# IOIO-NXT-V1.net
KiCad netlist of a schematic drawn in EAGLE
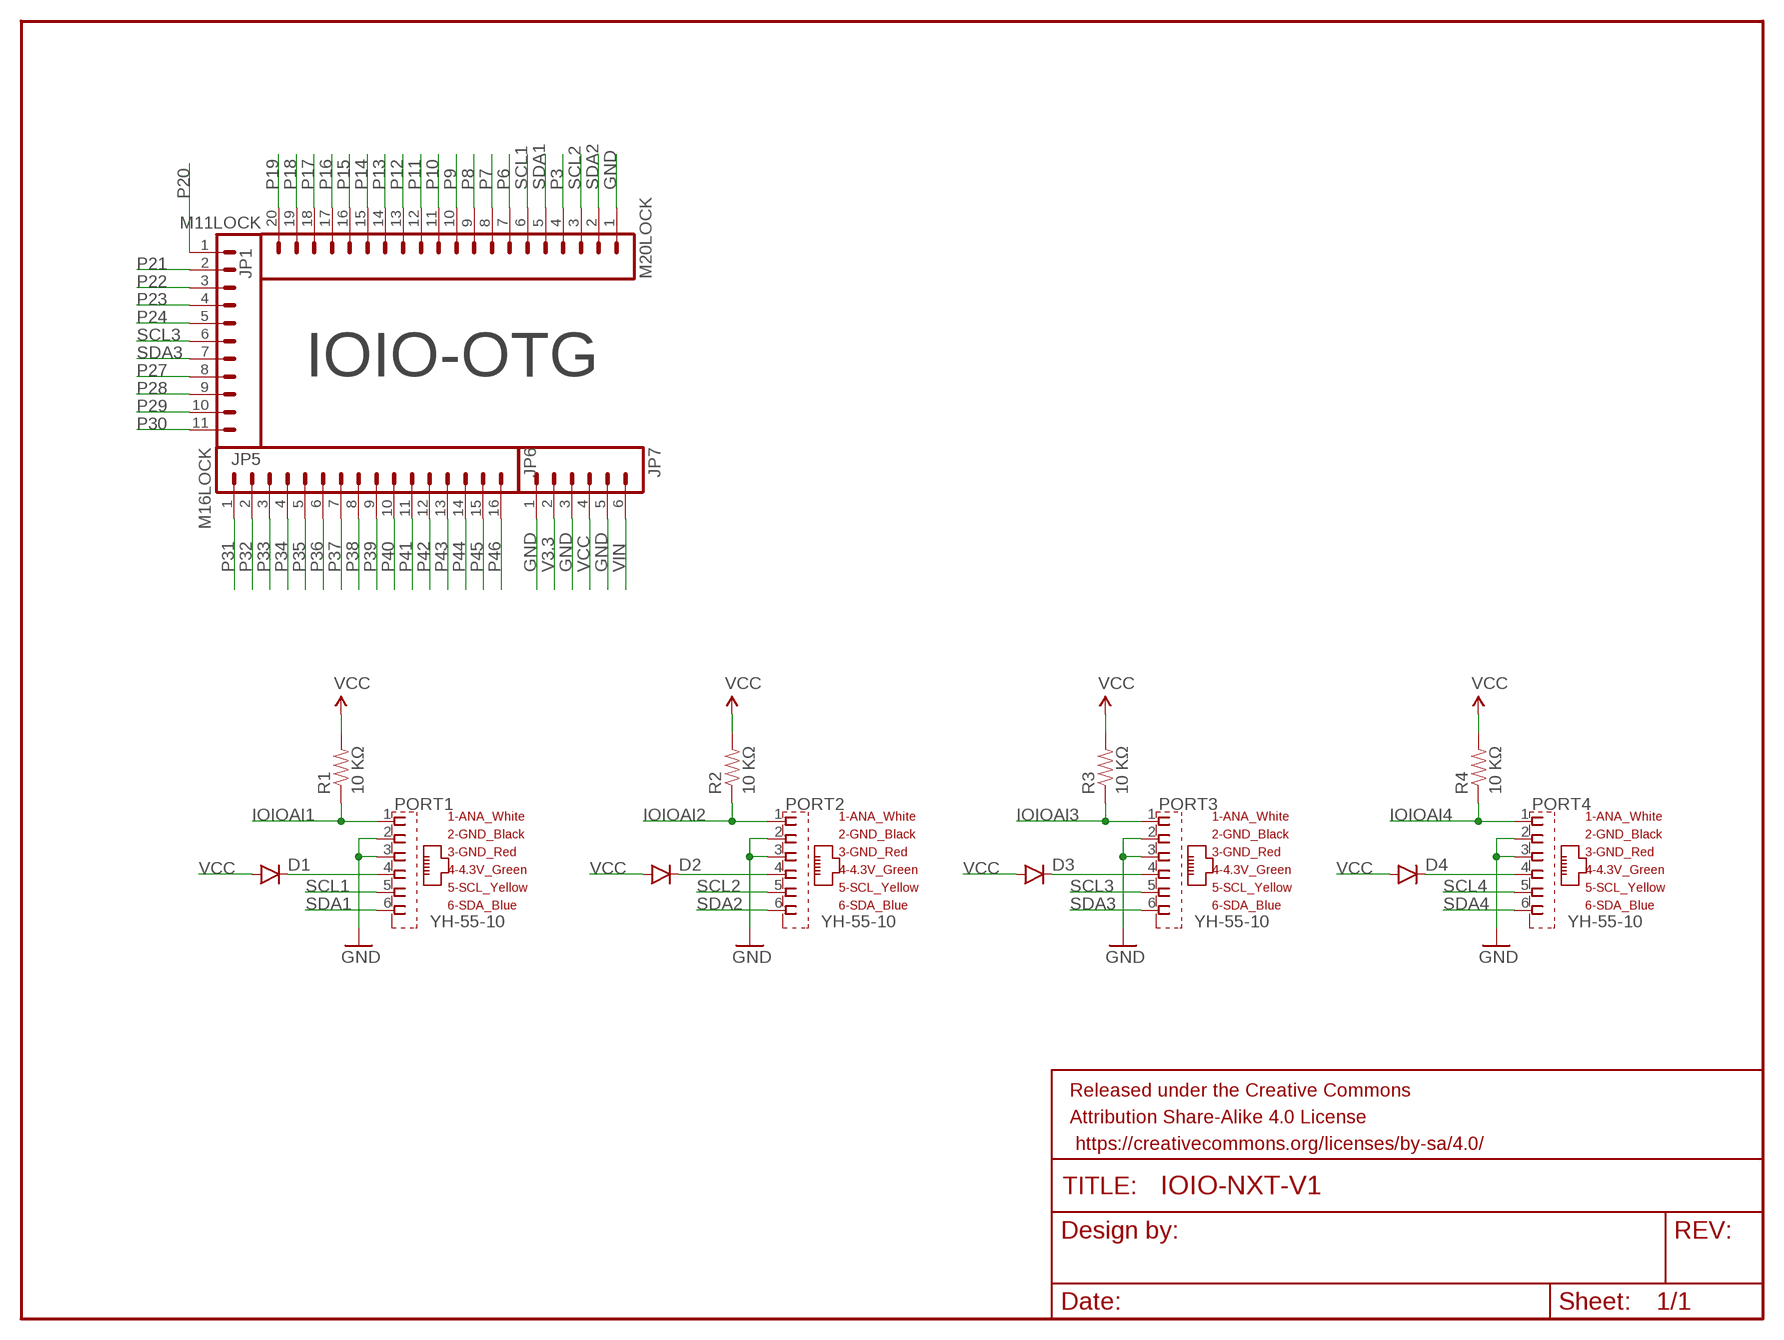
[diagram p0: schematic, sheet 1]

(export (version "E")
  (design (tool "Eeschema 10.0.6"))
  (components
    (comp (ref "D1")
      (value "DIODE")
      (footprint "eagle-import:DIODE-1N4001-KIT")
      (libsource (lib "eagle-import") (part "DIODE"))
    )
    (comp (ref "D2")
      (value "DIODE")
      (footprint "eagle-import:DIODE-1N4001-KIT")
      (libsource (lib "eagle-import") (part "DIODE"))
    )
    (comp (ref "D3")
      (value "DIODE")
      (footprint "eagle-import:DIODE-1N4001-KIT")
      (libsource (lib "eagle-import") (part "DIODE"))
    )
    (comp (ref "D4")
      (value "DIODE")
      (footprint "eagle-import:DIODE-1N4001-KIT")
      (libsource (lib "eagle-import") (part "DIODE"))
    )
    (comp (ref "FRAME1")
      (value "FRAME-LETTER")
      (footprint "eagle-import:CREATIVE_COMMONS")
      (libsource (lib "eagle-import") (part "FRAME-LETTER"))
    )
    (comp (ref "JP1")
      (value "M20LOCK")
      (footprint "eagle-import:1X20_LOCK")
      (libsource (lib "eagle-import") (part "M20LOCK"))
    )
    (comp (ref "JP5")
      (value "M11LOCK")
      (footprint "eagle-import:1X11_LOCK")
      (libsource (lib "eagle-import") (part "M11LOCK"))
    )
    (comp (ref "JP6")
      (value "M16LOCK")
      (footprint "eagle-import:1X16_LOCK")
      (libsource (lib "eagle-import") (part "M16LOCK"))
    )
    (comp (ref "JP7")
      (value "M06LOCK")
      (footprint "eagle-import:1X06_LOCK")
      (libsource (lib "eagle-import") (part "M06LOCK"))
    )
    (comp (ref "PORT1")
      (value "YH-55-10")
      (footprint "eagle-import:YH-55-10")
      (libsource (lib "eagle-import") (part "YH-55-10"))
    )
    (comp (ref "PORT2")
      (value "YH-55-10")
      (footprint "eagle-import:YH-55-10")
      (libsource (lib "eagle-import") (part "YH-55-10"))
    )
    (comp (ref "PORT3")
      (value "YH-55-10")
      (footprint "eagle-import:YH-55-10")
      (libsource (lib "eagle-import") (part "YH-55-10"))
    )
    (comp (ref "PORT4")
      (value "YH-55-10")
      (footprint "eagle-import:YH-55-10")
      (libsource (lib "eagle-import") (part "YH-55-10"))
    )
    (comp (ref "R1")
      (value "10 KΩ")
      (footprint "eagle-import:AXIAL-0.4")
      (libsource (lib "eagle-import") (part "RESISTORPTH-1/4W"))
    )
    (comp (ref "R2")
      (value "10 KΩ")
      (footprint "eagle-import:AXIAL-0.4")
      (libsource (lib "eagle-import") (part "RESISTORPTH-1/4W"))
    )
    (comp (ref "R3")
      (value "10 KΩ")
      (footprint "eagle-import:AXIAL-0.4")
      (libsource (lib "eagle-import") (part "RESISTORPTH-1/4W"))
    )
    (comp (ref "R4")
      (value "10 KΩ")
      (footprint "eagle-import:AXIAL-0.4")
      (libsource (lib "eagle-import") (part "RESISTORPTH-1/4W"))
    )
  )
  (nets
    (net (code "1") (name "/IOIOAI1") (class "Default")
      (node (ref "PORT1") (pin "1") (pinfunction "1_ANA_WHITE_1") (pintype "passive"))
      (node (ref "R1") (pin "P$1") (pinfunction "1_P$1") (pintype "passive"))
    )
    (net (code "2") (name "/IOIOAI2") (class "Default")
      (node (ref "PORT2") (pin "1") (pinfunction "1_ANA_WHITE_1") (pintype "passive"))
      (node (ref "R2") (pin "P$1") (pinfunction "1_P$1") (pintype "passive"))
    )
    (net (code "3") (name "/IOIOAI3") (class "Default")
      (node (ref "PORT3") (pin "1") (pinfunction "1_ANA_WHITE_1") (pintype "passive"))
      (node (ref "R3") (pin "P$1") (pinfunction "1_P$1") (pintype "passive"))
    )
    (net (code "4") (name "/IOIOAI4") (class "Default")
      (node (ref "PORT4") (pin "1") (pinfunction "1_ANA_WHITE_1") (pintype "passive"))
      (node (ref "R4") (pin "P$1") (pinfunction "1_P$1") (pintype "passive"))
    )
    (net (code "5") (name "/P3") (class "Default")
      (node (ref "JP1") (pin "4") (pinfunction "4_4") (pintype "passive"))
    )
    (net (code "6") (name "/P6") (class "Default")
      (node (ref "JP1") (pin "7") (pinfunction "7_7") (pintype "passive"))
    )
    (net (code "7") (name "/P7") (class "Default")
      (node (ref "JP1") (pin "8") (pinfunction "8_8") (pintype "passive"))
    )
    (net (code "8") (name "/P8") (class "Default")
      (node (ref "JP1") (pin "9") (pinfunction "9_9") (pintype "passive"))
    )
    (net (code "9") (name "/P9") (class "Default")
      (node (ref "JP1") (pin "10") (pinfunction "10_10") (pintype "passive"))
    )
    (net (code "10") (name "/P10") (class "Default")
      (node (ref "JP1") (pin "11") (pinfunction "11_11") (pintype "passive"))
    )
    (net (code "11") (name "/P11") (class "Default")
      (node (ref "JP1") (pin "12") (pinfunction "12_12") (pintype "passive"))
    )
    (net (code "12") (name "/P12") (class "Default")
      (node (ref "JP1") (pin "13") (pinfunction "13_13") (pintype "passive"))
    )
    (net (code "13") (name "/P13") (class "Default")
      (node (ref "JP1") (pin "14") (pinfunction "14_14") (pintype "passive"))
    )
    (net (code "14") (name "/P14") (class "Default")
      (node (ref "JP1") (pin "15") (pinfunction "15_15") (pintype "passive"))
    )
    (net (code "15") (name "/P15") (class "Default")
      (node (ref "JP1") (pin "16") (pinfunction "16_16") (pintype "passive"))
    )
    (net (code "16") (name "/P16") (class "Default")
      (node (ref "JP1") (pin "17") (pinfunction "17_17") (pintype "passive"))
    )
    (net (code "17") (name "/P17") (class "Default")
      (node (ref "JP1") (pin "18") (pinfunction "18_18") (pintype "passive"))
    )
    (net (code "18") (name "/P18") (class "Default")
      (node (ref "JP1") (pin "19") (pinfunction "19_19") (pintype "passive"))
    )
    (net (code "19") (name "/P19") (class "Default")
      (node (ref "JP1") (pin "20") (pinfunction "20_20") (pintype "passive"))
    )
    (net (code "20") (name "/P20") (class "Default")
      (node (ref "JP5") (pin "1") (pinfunction "1_1") (pintype "passive"))
    )
    (net (code "21") (name "/P21") (class "Default")
      (node (ref "JP5") (pin "2") (pinfunction "2_2") (pintype "passive"))
    )
    (net (code "22") (name "/P22") (class "Default")
      (node (ref "JP5") (pin "3") (pinfunction "3_3") (pintype "passive"))
    )
    (net (code "23") (name "/P23") (class "Default")
      (node (ref "JP5") (pin "4") (pinfunction "4_4") (pintype "passive"))
    )
    (net (code "24") (name "/P24") (class "Default")
      (node (ref "JP5") (pin "5") (pinfunction "5_5") (pintype "passive"))
    )
    (net (code "25") (name "/P27") (class "Default")
      (node (ref "JP5") (pin "8") (pinfunction "8_8") (pintype "passive"))
    )
    (net (code "26") (name "/P28") (class "Default")
      (node (ref "JP5") (pin "9") (pinfunction "9_9") (pintype "passive"))
    )
    (net (code "27") (name "/P29") (class "Default")
      (node (ref "JP5") (pin "10") (pinfunction "10_10") (pintype "passive"))
    )
    (net (code "28") (name "/P30") (class "Default")
      (node (ref "JP5") (pin "11") (pinfunction "11_11") (pintype "passive"))
    )
    (net (code "29") (name "/P31") (class "Default")
      (node (ref "JP6") (pin "1") (pinfunction "1_1") (pintype "passive"))
    )
    (net (code "30") (name "/P32") (class "Default")
      (node (ref "JP6") (pin "2") (pinfunction "2_2") (pintype "passive"))
    )
    (net (code "31") (name "/P33") (class "Default")
      (node (ref "JP6") (pin "3") (pinfunction "3_3") (pintype "passive"))
    )
    (net (code "32") (name "/P34") (class "Default")
      (node (ref "JP6") (pin "4") (pinfunction "4_4") (pintype "passive"))
    )
    (net (code "33") (name "/P35") (class "Default")
      (node (ref "JP6") (pin "5") (pinfunction "5_5") (pintype "passive"))
    )
    (net (code "34") (name "/P36") (class "Default")
      (node (ref "JP6") (pin "6") (pinfunction "6_6") (pintype "passive"))
    )
    (net (code "35") (name "/P37") (class "Default")
      (node (ref "JP6") (pin "7") (pinfunction "7_7") (pintype "passive"))
    )
    (net (code "36") (name "/P38") (class "Default")
      (node (ref "JP6") (pin "8") (pinfunction "8_8") (pintype "passive"))
    )
    (net (code "37") (name "/P39") (class "Default")
      (node (ref "JP6") (pin "9") (pinfunction "9_9") (pintype "passive"))
    )
    (net (code "38") (name "/P40") (class "Default")
      (node (ref "JP6") (pin "10") (pinfunction "10_10") (pintype "passive"))
    )
    (net (code "39") (name "/P41") (class "Default")
      (node (ref "JP6") (pin "11") (pinfunction "11_11") (pintype "passive"))
    )
    (net (code "40") (name "/P42") (class "Default")
      (node (ref "JP6") (pin "12") (pinfunction "12_12") (pintype "passive"))
    )
    (net (code "41") (name "/P43") (class "Default")
      (node (ref "JP6") (pin "13") (pinfunction "13_13") (pintype "passive"))
    )
    (net (code "42") (name "/P44") (class "Default")
      (node (ref "JP6") (pin "14") (pinfunction "14_14") (pintype "passive"))
    )
    (net (code "43") (name "/P45") (class "Default")
      (node (ref "JP6") (pin "15") (pinfunction "15_15") (pintype "passive"))
    )
    (net (code "44") (name "/P46") (class "Default")
      (node (ref "JP6") (pin "16") (pinfunction "16_16") (pintype "passive"))
    )
    (net (code "45") (name "/SCL1") (class "Default")
      (node (ref "JP1") (pin "6") (pinfunction "6_6") (pintype "passive"))
      (node (ref "PORT1") (pin "5") (pinfunction "5_SCL_YELLOW_5") (pintype "passive"))
    )
    (net (code "46") (name "/SCL2") (class "Default")
      (node (ref "JP1") (pin "3") (pinfunction "3_3") (pintype "passive"))
      (node (ref "PORT2") (pin "5") (pinfunction "5_SCL_YELLOW_5") (pintype "passive"))
    )
    (net (code "47") (name "/SCL3") (class "Default")
      (node (ref "JP5") (pin "6") (pinfunction "6_6") (pintype "passive"))
      (node (ref "PORT3") (pin "5") (pinfunction "5_SCL_YELLOW_5") (pintype "passive"))
    )
    (net (code "48") (name "/SCL4") (class "Default")
      (node (ref "PORT4") (pin "5") (pinfunction "5_SCL_YELLOW_5") (pintype "passive"))
    )
    (net (code "49") (name "/SDA1") (class "Default")
      (node (ref "JP1") (pin "5") (pinfunction "5_5") (pintype "passive"))
      (node (ref "PORT1") (pin "6") (pinfunction "6_SDA_BLUE_6") (pintype "passive"))
    )
    (net (code "50") (name "/SDA2") (class "Default")
      (node (ref "JP1") (pin "2") (pinfunction "2_2") (pintype "passive"))
      (node (ref "PORT2") (pin "6") (pinfunction "6_SDA_BLUE_6") (pintype "passive"))
    )
    (net (code "51") (name "/SDA3") (class "Default")
      (node (ref "JP5") (pin "7") (pinfunction "7_7") (pintype "passive"))
      (node (ref "PORT3") (pin "6") (pinfunction "6_SDA_BLUE_6") (pintype "passive"))
    )
    (net (code "52") (name "/SDA4") (class "Default")
      (node (ref "PORT4") (pin "6") (pinfunction "6_SDA_BLUE_6") (pintype "passive"))
    )
    (net (code "53") (name "/V3.3") (class "Default")
      (node (ref "JP7") (pin "2") (pinfunction "2_2") (pintype "passive"))
    )
    (net (code "54") (name "/VIN") (class "Default")
      (node (ref "JP7") (pin "6") (pinfunction "6_6") (pintype "passive"))
    )
    (net (code "55") (name "GND") (class "Default")
      (node (ref "JP1") (pin "1") (pinfunction "1_1") (pintype "passive"))
      (node (ref "JP7") (pin "1") (pinfunction "1_1") (pintype "passive"))
      (node (ref "JP7") (pin "3") (pinfunction "3_3") (pintype "passive"))
      (node (ref "JP7") (pin "5") (pinfunction "5_5") (pintype "passive"))
      (node (ref "PORT1") (pin "2") (pinfunction "2_GND_BLACK_2") (pintype "passive"))
      (node (ref "PORT1") (pin "3") (pinfunction "3_GND_RED_3") (pintype "passive"))
      (node (ref "PORT2") (pin "2") (pinfunction "2_GND_BLACK_2") (pintype "passive"))
      (node (ref "PORT2") (pin "3") (pinfunction "3_GND_RED_3") (pintype "passive"))
      (node (ref "PORT3") (pin "2") (pinfunction "2_GND_BLACK_2") (pintype "passive"))
      (node (ref "PORT3") (pin "3") (pinfunction "3_GND_RED_3") (pintype "passive"))
      (node (ref "PORT4") (pin "2") (pinfunction "2_GND_BLACK_2") (pintype "passive"))
      (node (ref "PORT4") (pin "3") (pinfunction "3_GND_RED_3") (pintype "passive"))
    )
    (net (code "56") (name "Net-(PORT1-4_4.3V_GREEN)") (class "Default")
      (node (ref "D1") (pin "C") (pinfunction "C_C") (pintype "passive"))
      (node (ref "PORT1") (pin "4") (pinfunction "4_4.3V_GREEN_4") (pintype "passive"))
    )
    (net (code "57") (name "Net-(PORT2-4_4.3V_GREEN)") (class "Default")
      (node (ref "D2") (pin "C") (pinfunction "C_C") (pintype "passive"))
      (node (ref "PORT2") (pin "4") (pinfunction "4_4.3V_GREEN_4") (pintype "passive"))
    )
    (net (code "58") (name "Net-(PORT3-4_4.3V_GREEN)") (class "Default")
      (node (ref "D3") (pin "C") (pinfunction "C_C") (pintype "passive"))
      (node (ref "PORT3") (pin "4") (pinfunction "4_4.3V_GREEN_4") (pintype "passive"))
    )
    (net (code "59") (name "Net-(PORT4-4_4.3V_GREEN)") (class "Default")
      (node (ref "D4") (pin "C") (pinfunction "C_C") (pintype "passive"))
      (node (ref "PORT4") (pin "4") (pinfunction "4_4.3V_GREEN_4") (pintype "passive"))
    )
    (net (code "60") (name "VCC") (class "Default")
      (node (ref "D1") (pin "A") (pinfunction "A_A") (pintype "passive"))
      (node (ref "D2") (pin "A") (pinfunction "A_A") (pintype "passive"))
      (node (ref "D3") (pin "A") (pinfunction "A_A") (pintype "passive"))
      (node (ref "D4") (pin "A") (pinfunction "A_A") (pintype "passive"))
      (node (ref "JP7") (pin "4") (pinfunction "4_4") (pintype "passive"))
      (node (ref "R1") (pin "P$2") (pinfunction "2_P$2") (pintype "passive"))
      (node (ref "R2") (pin "P$2") (pinfunction "2_P$2") (pintype "passive"))
      (node (ref "R3") (pin "P$2") (pinfunction "2_P$2") (pintype "passive"))
      (node (ref "R4") (pin "P$2") (pinfunction "2_P$2") (pintype "passive"))
    )
  )
)
